# ProPrj___2025-12-07.net
KiCad netlist of a schematic drawn in EasyEDA Pro
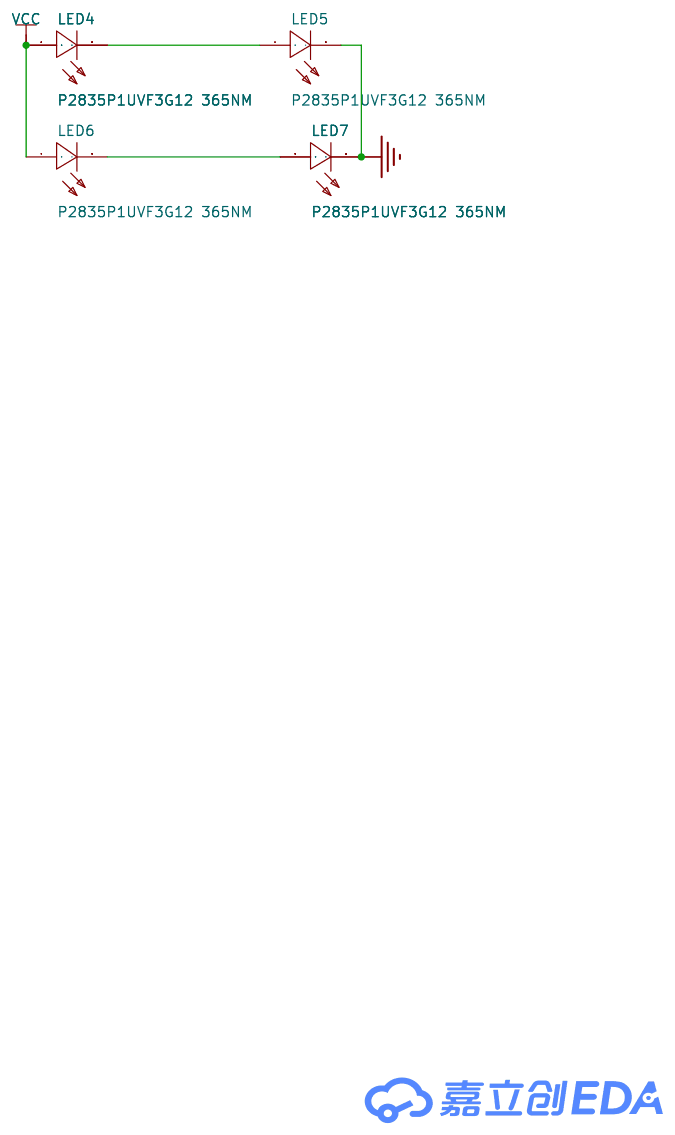
[diagram p0: schematic sheet]

(export (version "E")
  (design (tool "Eeschema 10.0.6"))
  (components
    (comp (ref "LED4")
      (value "P2835P1UVF3G12 365NM")
      (footprint "easyedapro:LED-SMD_L3.5-W2.8-R-RD_TJ-S2835UG5W8TLC6B-A5")
      (description "特性：封装尺寸 2.8 × 3.5 × 0.6 mm。 焊接方式：回流焊。 符合RoHS标准。 采用纯金线焊线。应用：灭蚊灯、美甲灯。 油墨、UV胶水、油漆等需要快速、高效固化的领域")
      (fields (field (name "Manufacturer") "Silverlight(银月光)"))
      (libsource (lib "easyedapro") (part "P2835P1UVF3G12 365NM"))
    )
    (comp (ref "LED5")
      (value "P2835P1UVF3G12 365NM")
      (footprint "easyedapro:LED-SMD_L3.5-W2.8-R-RD_TJ-S2835UG5W8TLC6B-A5")
      (description "特性：封装尺寸 2.8 × 3.5 × 0.6 mm。 焊接方式：回流焊。 符合RoHS标准。 采用纯金线焊线。应用：灭蚊灯、美甲灯。 油墨、UV胶水、油漆等需要快速、高效固化的领域")
      (fields (field (name "Manufacturer") "Silverlight(银月光)"))
      (libsource (lib "easyedapro") (part "P2835P1UVF3G12 365NM"))
    )
    (comp (ref "LED6")
      (value "P2835P1UVF3G12 365NM")
      (footprint "easyedapro:LED-SMD_L3.5-W2.8-R-RD_TJ-S2835UG5W8TLC6B-A5")
      (description "特性：封装尺寸 2.8 × 3.5 × 0.6 mm。 焊接方式：回流焊。 符合RoHS标准。 采用纯金线焊线。应用：灭蚊灯、美甲灯。 油墨、UV胶水、油漆等需要快速、高效固化的领域")
      (fields (field (name "Manufacturer") "Silverlight(银月光)"))
      (libsource (lib "easyedapro") (part "P2835P1UVF3G12 365NM"))
    )
    (comp (ref "LED7")
      (value "P2835P1UVF3G12 365NM")
      (footprint "easyedapro:LED-SMD_L3.5-W2.8-R-RD_TJ-S2835UG5W8TLC6B-A5")
      (description "特性：封装尺寸 2.8 × 3.5 × 0.6 mm。 焊接方式：回流焊。 符合RoHS标准。 采用纯金线焊线。应用：灭蚊灯、美甲灯。 油墨、UV胶水、油漆等需要快速、高效固化的领域")
      (fields (field (name "Manufacturer") "Silverlight(银月光)"))
      (libsource (lib "easyedapro") (part "P2835P1UVF3G12 365NM"))
    )
  )
  (nets
    (net (code "1") (name "GND") (class "Default")
      (node (ref "LED5") (pin "2") (pinfunction "-_2") (pintype "unspecified"))
      (node (ref "LED7") (pin "2") (pinfunction "-_2") (pintype "unspecified"))
    )
    (net (code "2") (name "Net-(LED4--)") (class "Default")
      (node (ref "LED4") (pin "2") (pinfunction "-_2") (pintype "unspecified"))
      (node (ref "LED5") (pin "1") (pinfunction "+_1") (pintype "unspecified"))
    )
    (net (code "3") (name "Net-(LED6--)") (class "Default")
      (node (ref "LED6") (pin "2") (pinfunction "-_2") (pintype "unspecified"))
      (node (ref "LED7") (pin "1") (pinfunction "+_1") (pintype "unspecified"))
    )
    (net (code "4") (name "VCC") (class "Default")
      (node (ref "LED4") (pin "1") (pinfunction "+_1") (pintype "unspecified"))
      (node (ref "LED6") (pin "1") (pinfunction "+_1") (pintype "unspecified"))
    )
  )
)
